# ESP8266-07-RGB.net
KiCad netlist of a schematic drawn in EAGLE
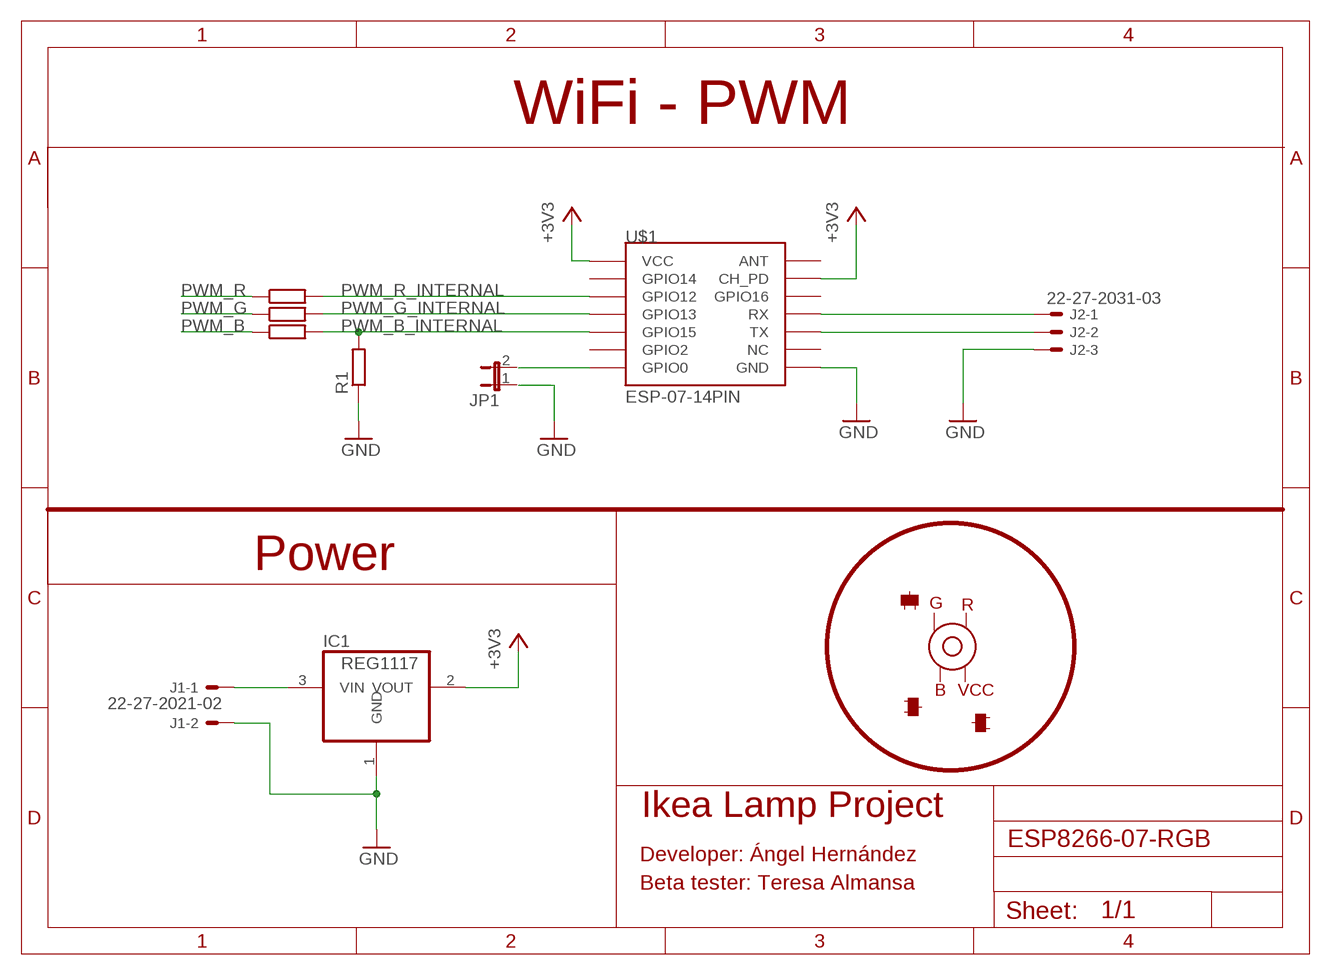
[diagram p0: schematic, sheet 1]

(export (version "E")
  (design (tool "Eeschema 10.0.6"))
  (components
    (comp (ref "IC1")
      (value "REG1117")
      (footprint "eagle-import:SOT223")
      (libsource (lib "eagle-import") (part "REG1117"))
    )
    (comp (ref "J1")
      (value "22-27-2021-02")
      (footprint "eagle-import:6410-02")
      (libsource (lib "eagle-import") (part "22-?-0227-2021"))
    )
    (comp (ref "J2")
      (value "22-27-2031-03")
      (footprint "eagle-import:6410-03")
      (libsource (lib "eagle-import") (part "22-?-0327-2031"))
    )
    (comp (ref "JP1")
      (value "JP1E")
      (footprint "eagle-import:JP1")
      (libsource (lib "eagle-import") (part "JP1E"))
    )
    (comp (ref "R1")
      (value "R-EU_0204/7")
      (footprint "eagle-import:0204_7")
      (libsource (lib "eagle-import") (part "R-EU_0204/7"))
    )
    (comp (ref "R2")
      (value "R-EU_0204/7")
      (footprint "eagle-import:0204_7")
      (libsource (lib "eagle-import") (part "R-EU_0204/7"))
    )
    (comp (ref "R3")
      (value "R-EU_0204/7")
      (footprint "eagle-import:0204_7")
      (libsource (lib "eagle-import") (part "R-EU_0204/7"))
    )
    (comp (ref "R4")
      (value "R-EU_0204/7")
      (footprint "eagle-import:0204_7")
      (libsource (lib "eagle-import") (part "R-EU_0204/7"))
    )
    (comp (ref "U$1")
      (value "ESP-07-14PIN")
      (footprint "eagle-import:ESP-07-14PIN")
      (libsource (lib "eagle-import") (part "ESP-07-14PIN"))
    )
  )
  (nets
    (net (code "1") (name "+3V3") (class "Default")
      (node (ref "IC1") (pin "2") (pinfunction "VOUT_2") (pintype "output"))
      (node (ref "U$1") (pin "CH_PD") (pinfunction "CH_PD_CH_PD") (pintype "bidirectional"))
      (node (ref "U$1") (pin "VCC") (pinfunction "VCC_VCC") (pintype "bidirectional"))
    )
    (net (code "2") (name "/PWM_B") (class "Default")
      (node (ref "R2") (pin "1") (pinfunction "1_1") (pintype "passive"))
    )
    (net (code "3") (name "/PWM_B_INTERNAL") (class "Default")
      (node (ref "R1") (pin "2") (pinfunction "2_2") (pintype "passive"))
      (node (ref "R2") (pin "2") (pinfunction "2_2") (pintype "passive"))
      (node (ref "U$1") (pin "GPIO15") (pinfunction "GPIO15_GPIO15") (pintype "bidirectional"))
    )
    (net (code "4") (name "/PWM_G") (class "Default")
      (node (ref "R3") (pin "1") (pinfunction "1_1") (pintype "passive"))
    )
    (net (code "5") (name "/PWM_G_INTERNAL") (class "Default")
      (node (ref "R3") (pin "2") (pinfunction "2_2") (pintype "passive"))
      (node (ref "U$1") (pin "GPIO13") (pinfunction "GPIO13_GPIO13") (pintype "bidirectional"))
    )
    (net (code "6") (name "/PWM_R") (class "Default")
      (node (ref "R4") (pin "1") (pinfunction "1_1") (pintype "passive"))
    )
    (net (code "7") (name "/PWM_R_INTERNAL") (class "Default")
      (node (ref "R4") (pin "2") (pinfunction "2_2") (pintype "passive"))
      (node (ref "U$1") (pin "GPIO12") (pinfunction "GPIO12_GPIO12") (pintype "bidirectional"))
    )
    (net (code "8") (name "GND") (class "Default")
      (node (ref "IC1") (pin "1") (pinfunction "GND_1") (pintype "power_in"))
      (node (ref "J1") (pin "2") (pinfunction "S_2") (pintype "passive"))
      (node (ref "J2") (pin "3") (pinfunction "S_3") (pintype "passive"))
      (node (ref "R1") (pin "1") (pinfunction "1_1") (pintype "passive"))
      (node (ref "U$1") (pin "GND") (pinfunction "GND_GND") (pintype "bidirectional"))
    )
    (net (code "9") (name "Net-(IC1-VIN)") (class "Default")
      (node (ref "IC1") (pin "3") (pinfunction "VIN_3") (pintype "input"))
      (node (ref "J1") (pin "1") (pinfunction "S_1") (pintype "passive"))
    )
    (net (code "10") (name "Net-(J2A-S)") (class "Default")
      (node (ref "J2") (pin "1") (pinfunction "S_1") (pintype "passive"))
      (node (ref "U$1") (pin "RX") (pinfunction "RX_RX") (pintype "bidirectional"))
    )
    (net (code "11") (name "Net-(J2B-S)") (class "Default")
      (node (ref "J2") (pin "2") (pinfunction "S_2") (pintype "passive"))
      (node (ref "U$1") (pin "TX") (pinfunction "TX_TX") (pintype "bidirectional"))
    )
    (net (code "12") (name "unconnected-(JP1-Pad1)") (class "Default")
      (node (ref "JP1") (pin "1") (pinfunction "1_1") (pintype "passive"))
    )
    (net (code "13") (name "unconnected-(JP1-Pad2)") (class "Default")
      (node (ref "JP1") (pin "2") (pinfunction "2_2") (pintype "passive"))
    )
    (net (code "14") (name "unconnected-(U$1-PadANT)") (class "Default")
      (node (ref "U$1") (pin "ANT") (pinfunction "ANT_ANT") (pintype "bidirectional"))
    )
    (net (code "15") (name "unconnected-(U$1-PadGPIO0)") (class "Default")
      (node (ref "U$1") (pin "GPIO0") (pinfunction "GPIO0_GPIO0") (pintype "bidirectional"))
    )
    (net (code "16") (name "unconnected-(U$1-PadGPIO2)") (class "Default")
      (node (ref "U$1") (pin "GPIO2") (pinfunction "GPIO2_GPIO2") (pintype "bidirectional"))
    )
    (net (code "17") (name "unconnected-(U$1-PadGPIO14)") (class "Default")
      (node (ref "U$1") (pin "GPIO14") (pinfunction "GPIO14_GPIO14") (pintype "bidirectional"))
    )
    (net (code "18") (name "unconnected-(U$1-PadGPIO16)") (class "Default")
      (node (ref "U$1") (pin "GPIO16") (pinfunction "GPIO16_GPIO16") (pintype "bidirectional"))
    )
    (net (code "19") (name "unconnected-(U$1-PadNC)") (class "Default")
      (node (ref "U$1") (pin "NC") (pinfunction "NC_NC") (pintype "bidirectional"))
    )
  )
)
